# schematic.net
KiCad netlist of a schematic drawn in EasyEDA
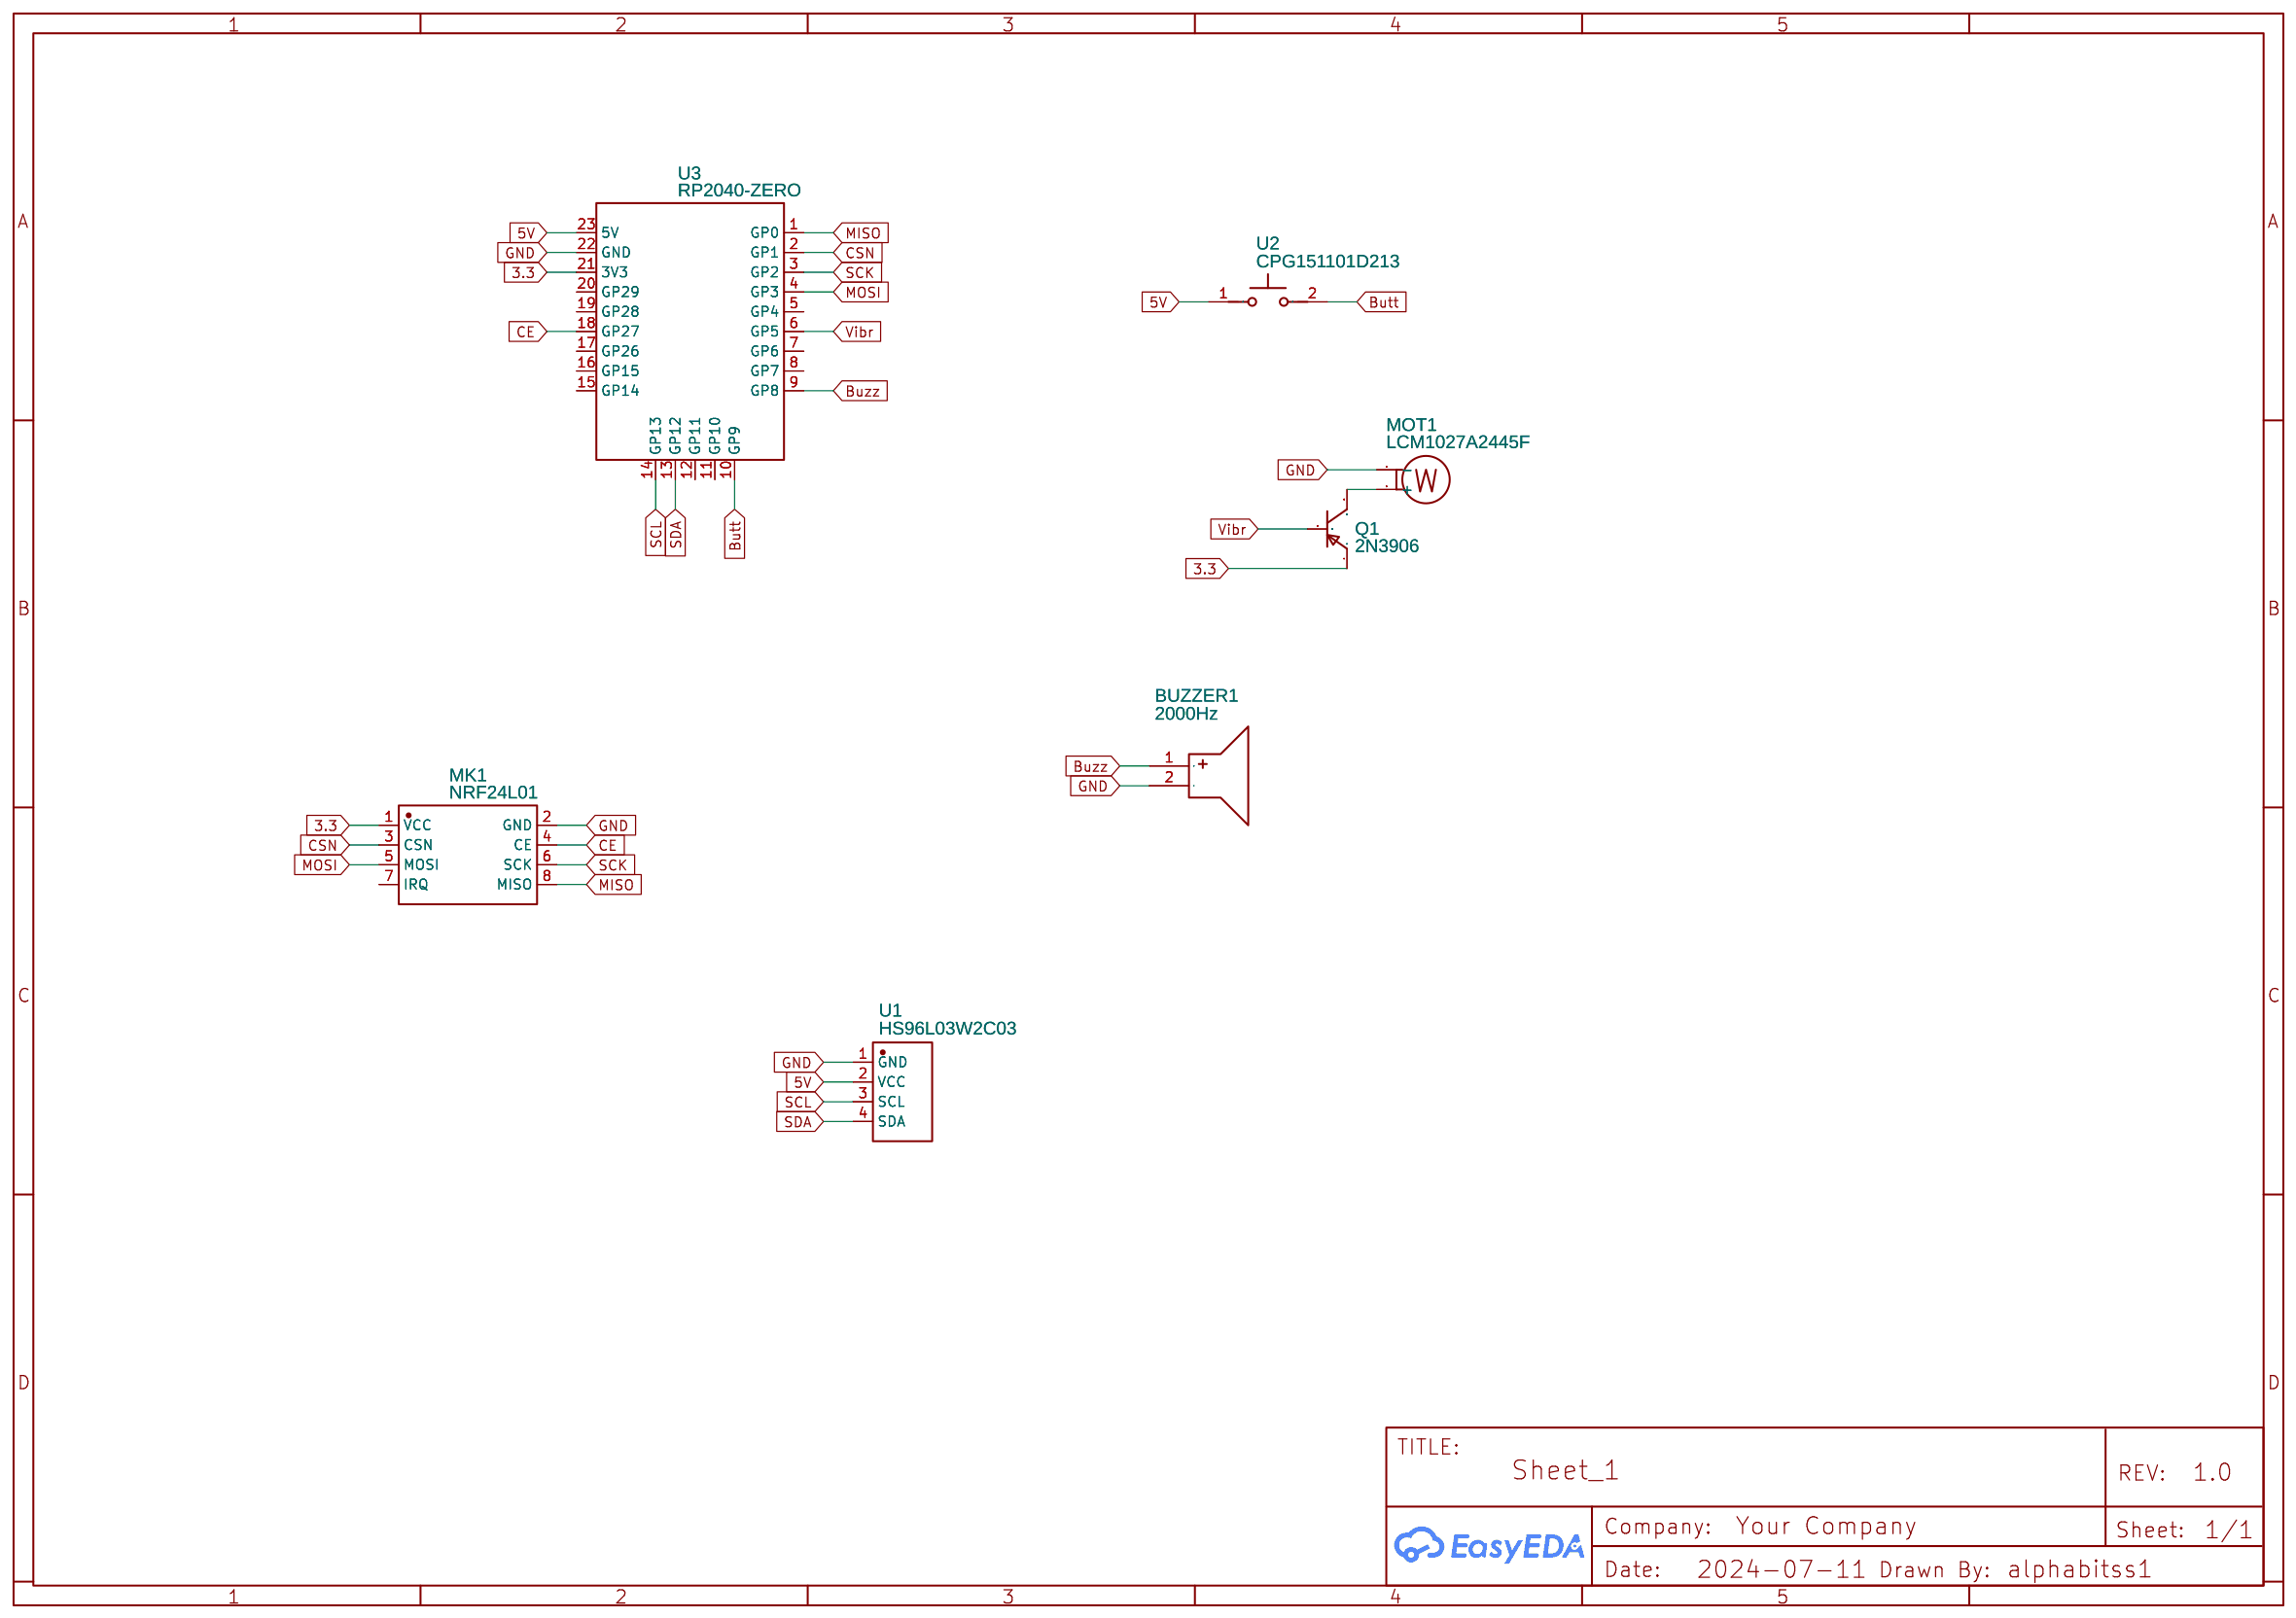
[diagram p0: schematic sheet]

(export (version "E")
  (design (tool "Eeschema 10.0.6"))
  (components
    (comp (ref "BUZZER1")
      (value "2000Hz")
      (fields (field (name "Manufacturer Part") "FS1265-05") (field (name "Manufacturer") "FUET(福声科技)"))
      (libsource (lib "") (part "FS1265-05"))
    )
    (comp (ref "MK1")
      (value "NRF24L01")
      (fields (field (name "Manufacturer Part") "NF-04") (field (name "Manufacturer") "Ai-Thinker(安信可)"))
      (libsource (lib "") (part "NRF24L01"))
    )
    (comp (ref "MOT1")
      (value "LCM1027A2445F")
      (fields (field (name "Manufacturer") "LEADER(立得)"))
      (libsource (lib "") (part "LCM1027A2445F"))
    )
    (comp (ref "Q1")
      (value "2N3906")
      (fields (field (name "Manufacturer") "CJ(江苏长电/长晶)"))
      (libsource (lib "") (part "2N3906"))
    )
    (comp (ref "U1")
      (value "HS96L03W2C03")
      (fields (field (name "Manufacturer") "HS(汉昇)"))
      (libsource (lib "") (part "HS96L03W2C03"))
    )
    (comp (ref "U2")
      (value "CPG151101D213")
      (fields (field (name "Manufacturer") "Kailh(凯华)"))
      (libsource (lib "") (part "CPG151101D213"))
    )
    (comp (ref "U3")
      (value "RP2040-ZERO")
      (fields
        (field (name "Manufacturer Part") "RP2040-Zero")
        (field (name "Manufacturer") "Waveshare(微雪电子)")
      )
      (libsource (lib "") (part "RP2040-ZERO"))
    )
  )
  (nets
    (net (code "1") (name "3.3") (class "Default")
      (node (ref "MK1") (pin "1") (pinfunction "VCC_1") (pintype "unspecified"))
      (node (ref "Q1") (pin "1") (pinfunction "E_1") (pintype "unspecified"))
      (node (ref "U3") (pin "21") (pinfunction "3V3_21") (pintype "unspecified"))
    )
    (net (code "2") (name "5V") (class "Default")
      (node (ref "U1") (pin "2") (pinfunction "VCC_2") (pintype "unspecified"))
      (node (ref "U2") (pin "1") (pinfunction "1_1") (pintype "unspecified"))
      (node (ref "U3") (pin "23") (pinfunction "5V_23") (pintype "unspecified"))
    )
    (net (code "3") (name "Butt") (class "Default")
      (node (ref "U2") (pin "2") (pinfunction "2_2") (pintype "unspecified"))
      (node (ref "U3") (pin "10") (pinfunction "GP9_10") (pintype "unspecified"))
    )
    (net (code "4") (name "Buzz") (class "Default")
      (node (ref "BUZZER1") (pin "1") (pinfunction "+_1") (pintype "unspecified"))
      (node (ref "U3") (pin "9") (pinfunction "GP8_9") (pintype "unspecified"))
    )
    (net (code "5") (name "CE") (class "Default")
      (node (ref "MK1") (pin "4") (pinfunction "CE_4") (pintype "unspecified"))
      (node (ref "U3") (pin "18") (pinfunction "GP27_18") (pintype "unspecified"))
    )
    (net (code "6") (name "CSN") (class "Default")
      (node (ref "MK1") (pin "3") (pinfunction "CSN_3") (pintype "unspecified"))
      (node (ref "U3") (pin "2") (pinfunction "GP1_2") (pintype "unspecified"))
    )
    (net (code "7") (name "GND") (class "Default")
      (node (ref "BUZZER1") (pin "2") (pinfunction "-_2") (pintype "unspecified"))
      (node (ref "MK1") (pin "2") (pinfunction "GND_2") (pintype "unspecified"))
      (node (ref "MOT1") (pin "1") (pinfunction "-_1") (pintype "unspecified"))
      (node (ref "U1") (pin "1") (pinfunction "GND_1") (pintype "unspecified"))
      (node (ref "U3") (pin "22") (pinfunction "GND_22") (pintype "unspecified"))
    )
    (net (code "8") (name "MISO") (class "Default")
      (node (ref "MK1") (pin "8") (pinfunction "MISO_8") (pintype "unspecified"))
      (node (ref "U3") (pin "1") (pinfunction "GP0_1") (pintype "unspecified"))
    )
    (net (code "9") (name "MOSI") (class "Default")
      (node (ref "MK1") (pin "5") (pinfunction "MOSI_5") (pintype "unspecified"))
      (node (ref "U3") (pin "4") (pinfunction "GP3_4") (pintype "unspecified"))
    )
    (net (code "10") (name "Net-(MOT1-+)") (class "Default")
      (node (ref "MOT1") (pin "2") (pinfunction "+_2") (pintype "unspecified"))
      (node (ref "Q1") (pin "3") (pinfunction "C_3") (pintype "unspecified"))
    )
    (net (code "11") (name "SCK") (class "Default")
      (node (ref "MK1") (pin "6") (pinfunction "SCK_6") (pintype "unspecified"))
      (node (ref "U3") (pin "3") (pinfunction "GP2_3") (pintype "unspecified"))
    )
    (net (code "12") (name "SCL") (class "Default")
      (node (ref "U1") (pin "3") (pinfunction "SCL_3") (pintype "unspecified"))
      (node (ref "U3") (pin "14") (pinfunction "GP13_14") (pintype "unspecified"))
    )
    (net (code "13") (name "SDA") (class "Default")
      (node (ref "U1") (pin "4") (pinfunction "SDA_4") (pintype "unspecified"))
      (node (ref "U3") (pin "13") (pinfunction "GP12_13") (pintype "unspecified"))
    )
    (net (code "14") (name "Vibr") (class "Default")
      (node (ref "Q1") (pin "2") (pinfunction "B_2") (pintype "unspecified"))
      (node (ref "U3") (pin "6") (pinfunction "GP5_6") (pintype "unspecified"))
    )
    (net (code "15") (name "unconnected-(MK1-IRQ-Pad7)") (class "Default")
      (node (ref "MK1") (pin "7") (pinfunction "IRQ_7") (pintype "unspecified"))
    )
    (net (code "16") (name "unconnected-(U3-GP4-Pad5)") (class "Default")
      (node (ref "U3") (pin "5") (pinfunction "GP4_5") (pintype "unspecified"))
    )
    (net (code "17") (name "unconnected-(U3-GP6-Pad7)") (class "Default")
      (node (ref "U3") (pin "7") (pinfunction "GP6_7") (pintype "unspecified"))
    )
    (net (code "18") (name "unconnected-(U3-GP7-Pad8)") (class "Default")
      (node (ref "U3") (pin "8") (pinfunction "GP7_8") (pintype "unspecified"))
    )
    (net (code "19") (name "unconnected-(U3-GP10-Pad11)") (class "Default")
      (node (ref "U3") (pin "11") (pinfunction "GP10_11") (pintype "unspecified"))
    )
    (net (code "20") (name "unconnected-(U3-GP11-Pad12)") (class "Default")
      (node (ref "U3") (pin "12") (pinfunction "GP11_12") (pintype "unspecified"))
    )
    (net (code "21") (name "unconnected-(U3-GP14-Pad15)") (class "Default")
      (node (ref "U3") (pin "15") (pinfunction "GP14_15") (pintype "unspecified"))
    )
    (net (code "22") (name "unconnected-(U3-GP15-Pad16)") (class "Default")
      (node (ref "U3") (pin "16") (pinfunction "GP15_16") (pintype "unspecified"))
    )
    (net (code "23") (name "unconnected-(U3-GP26-Pad17)") (class "Default")
      (node (ref "U3") (pin "17") (pinfunction "GP26_17") (pintype "unspecified"))
    )
    (net (code "24") (name "unconnected-(U3-GP28-Pad19)") (class "Default")
      (node (ref "U3") (pin "19") (pinfunction "GP28_19") (pintype "unspecified"))
    )
    (net (code "25") (name "unconnected-(U3-GP29-Pad20)") (class "Default")
      (node (ref "U3") (pin "20") (pinfunction "GP29_20") (pintype "unspecified"))
    )
  )
)
